# connector.net
KiCad netlist of a schematic drawn in Altium Designer
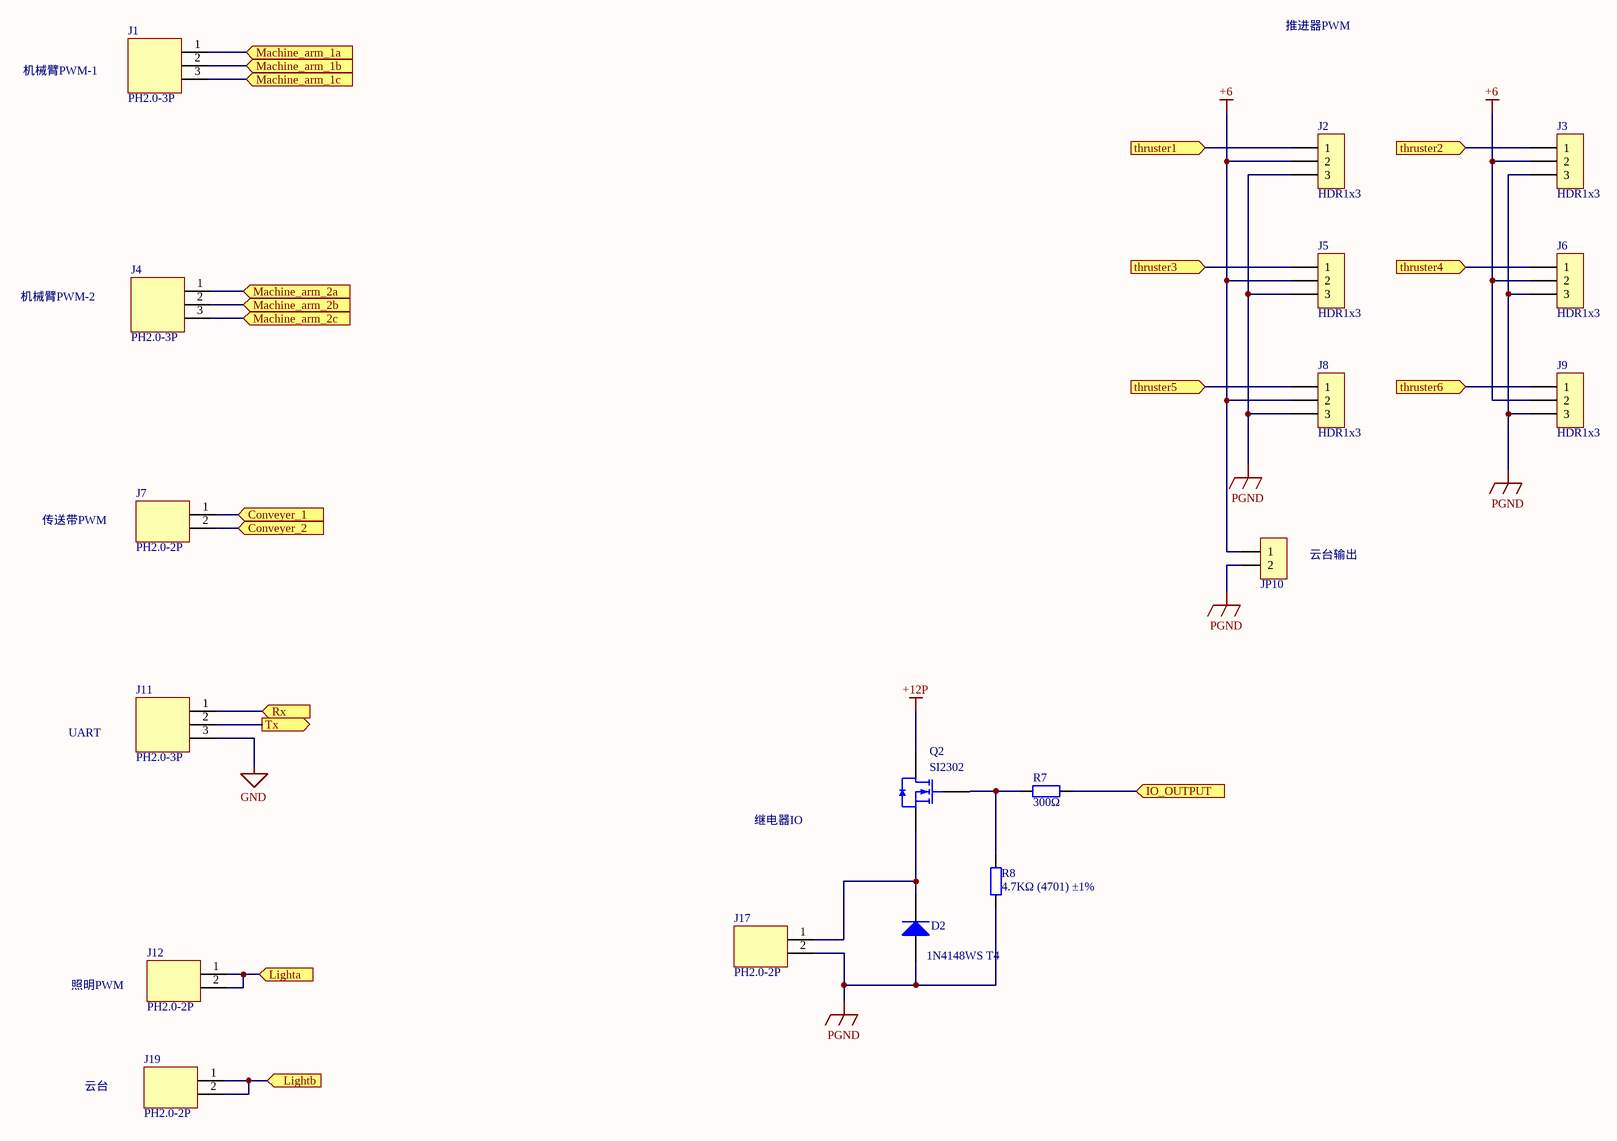
[diagram p0: connector.SchDoc]

(export (version "E")
  (design (tool "Eeschema 10.0.6"))
  (components
    (comp (ref "D2")
      (value "1N4148WS T4")
      (footprint "SOD-323")
      (description "二极管")
      (libsource (lib "Miscellaneous Devices LC") (part "SOD-323 1N4148WS T4"))
    )
    (comp (ref "J1") (value "PH2.0-3P") (footprint "PH2.0-3P") (libsource (lib "PH") (part "PH2.0-3P")))
    (comp (ref "J2")
      (value "HDR1x3")
      (footprint "PIN-3-2.54-1.0")
      (description "Connector")
      (libsource (lib "General") (part "HDR1x3"))
    )
    (comp (ref "J3")
      (value "HDR1x3")
      (footprint "PIN-3-2.54-1.0")
      (description "Connector")
      (libsource (lib "General") (part "HDR1x3"))
    )
    (comp (ref "J4") (value "PH2.0-3P") (footprint "PH2.0-3P") (libsource (lib "PH") (part "PH2.0-3P")))
    (comp (ref "J5")
      (value "HDR1x3")
      (footprint "PIN-3-2.54-1.0")
      (description "Connector")
      (libsource (lib "General") (part "HDR1x3"))
    )
    (comp (ref "J6")
      (value "HDR1x3")
      (footprint "PIN-3-2.54-1.0")
      (description "Connector")
      (libsource (lib "General") (part "HDR1x3"))
    )
    (comp (ref "J7") (value "PH2.0-2P") (footprint "PH2.0-2P") (libsource (lib "PH") (part "PH2.0-2P")))
    (comp (ref "J8")
      (value "HDR1x3")
      (footprint "PIN-3-2.54-1.0")
      (description "Connector")
      (libsource (lib "General") (part "HDR1x3"))
    )
    (comp (ref "J9")
      (value "HDR1x3")
      (footprint "PIN-3-2.54-1.0")
      (description "Connector")
      (libsource (lib "General") (part "HDR1x3"))
    )
    (comp (ref "J11") (value "PH2.0-3P") (footprint "PH2.0-3P") (libsource (lib "PH") (part "PH2.0-3P")))
    (comp (ref "J12") (value "PH2.0-2P") (footprint "PH2.0-2P") (libsource (lib "PH") (part "PH2.0-2P")))
    (comp (ref "J17") (value "PH2.0-2P") (footprint "PH2.0-2P") (libsource (lib "PH") (part "PH2.0-2P")))
    (comp (ref "J19") (value "PH2.0-2P") (footprint "PH2.0-2P") (libsource (lib "PH") (part "PH2.0-2P")))
    (comp (ref "JP10")
      (value "HDR-1X2")
      (footprint "KF128-5.08-2P")
      (description "2P接插件")
      (fields (field (name "版权归属") "源创客"))
      (libsource (lib "4.10 - 接插件-脚距5.08") (part "Header 2"))
    )
    (comp (ref "Q2")
      (value "SI2302")
      (footprint "SOT-23(SOT-23-3)")
      (description "MOS(场效应管)")
      (libsource (lib "Miscellaneous Devices LC") (part "2N7002 7002"))
    )
    (comp (ref "R7")
      (value "300Ω")
      (footprint "0603_R")
      (description "贴片电阻")
      (libsource (lib "Miscellaneous Devices LC") (part "0603 10KΩ (1002) 1%"))
    )
    (comp (ref "R8")
      (value "4.7KΩ (4701) ±1%")
      (footprint "0603_R")
      (description "贴片电阻")
      (libsource (lib "Miscellaneous Devices LC") (part "0603 4.7KΩ (4701) 1%"))
    )
  )
  (nets
    (net (code "1") (name "+6") (class "Default")
      (node (ref "J2") (pin "2") (pinfunction "2_2") (pintype "passive"))
      (node (ref "J3") (pin "2") (pinfunction "2_2") (pintype "passive"))
      (node (ref "J5") (pin "2") (pinfunction "2_2") (pintype "passive"))
      (node (ref "J6") (pin "2") (pinfunction "2_2") (pintype "passive"))
      (node (ref "J8") (pin "2") (pinfunction "2_2") (pintype "passive"))
      (node (ref "J9") (pin "2") (pinfunction "2_2") (pintype "passive"))
      (node (ref "JP10") (pin "1") (pinfunction "1_1") (pintype "passive"))
    )
    (net (code "2") (name "+12P") (class "Default")
      (node (ref "Q2") (pin "3") (pinfunction "D_3") (pintype "passive"))
    )
    (net (code "3") (name "/Conveyer_1") (class "Default")
      (node (ref "J7") (pin "1") (pinfunction "1_1") (pintype "passive"))
    )
    (net (code "4") (name "/Conveyer_2") (class "Default")
      (node (ref "J7") (pin "2") (pinfunction "2_2") (pintype "passive"))
    )
    (net (code "5") (name "/IO_OUTPUT") (class "Default")
      (node (ref "R7") (pin "2") (pinfunction "2_2") (pintype "passive"))
    )
    (net (code "6") (name "/Lighta") (class "Default")
      (node (ref "J12") (pin "1") (pinfunction "1_1") (pintype "passive"))
      (node (ref "J12") (pin "2") (pinfunction "2_2") (pintype "passive"))
    )
    (net (code "7") (name "/Lightb") (class "Default")
      (node (ref "J19") (pin "1") (pinfunction "1_1") (pintype "passive"))
      (node (ref "J19") (pin "2") (pinfunction "2_2") (pintype "passive"))
    )
    (net (code "8") (name "/Machine_arm_1a") (class "Default")
      (node (ref "J1") (pin "1") (pinfunction "1_1") (pintype "passive"))
    )
    (net (code "9") (name "/Machine_arm_1b") (class "Default")
      (node (ref "J1") (pin "2") (pinfunction "2_2") (pintype "passive"))
    )
    (net (code "10") (name "/Machine_arm_1c") (class "Default")
      (node (ref "J1") (pin "3") (pinfunction "3_3") (pintype "passive"))
    )
    (net (code "11") (name "/Machine_arm_2a") (class "Default")
      (node (ref "J4") (pin "1") (pinfunction "1_1") (pintype "passive"))
    )
    (net (code "12") (name "/Machine_arm_2b") (class "Default")
      (node (ref "J4") (pin "2") (pinfunction "2_2") (pintype "passive"))
    )
    (net (code "13") (name "/Machine_arm_2c") (class "Default")
      (node (ref "J4") (pin "3") (pinfunction "3_3") (pintype "passive"))
    )
    (net (code "14") (name "/Rx") (class "Default")
      (node (ref "J11") (pin "1") (pinfunction "1_1") (pintype "passive"))
    )
    (net (code "15") (name "/Tx") (class "Default")
      (node (ref "J11") (pin "2") (pinfunction "2_2") (pintype "passive"))
    )
    (net (code "16") (name "/thruster1") (class "Default")
      (node (ref "J2") (pin "1") (pinfunction "1_1") (pintype "passive"))
    )
    (net (code "17") (name "/thruster2") (class "Default")
      (node (ref "J3") (pin "1") (pinfunction "1_1") (pintype "passive"))
    )
    (net (code "18") (name "/thruster3") (class "Default")
      (node (ref "J5") (pin "1") (pinfunction "1_1") (pintype "passive"))
    )
    (net (code "19") (name "/thruster4") (class "Default")
      (node (ref "J6") (pin "1") (pinfunction "1_1") (pintype "passive"))
    )
    (net (code "20") (name "/thruster5") (class "Default")
      (node (ref "J8") (pin "1") (pinfunction "1_1") (pintype "passive"))
    )
    (net (code "21") (name "/thruster6") (class "Default")
      (node (ref "J9") (pin "1") (pinfunction "1_1") (pintype "passive"))
    )
    (net (code "22") (name "GND") (class "Default")
      (node (ref "J11") (pin "3") (pinfunction "3_3") (pintype "passive"))
    )
    (net (code "23") (name "Net-(D2-K)") (class "Default")
      (node (ref "D2") (pin "2") (pinfunction "K_2") (pintype "passive"))
      (node (ref "J17") (pin "1") (pinfunction "1_1") (pintype "passive"))
      (node (ref "Q2") (pin "2") (pinfunction "S_2") (pintype "passive"))
    )
    (net (code "24") (name "Net-(Q2-G)") (class "Default")
      (node (ref "Q2") (pin "1") (pinfunction "G_1") (pintype "passive"))
      (node (ref "R7") (pin "1") (pinfunction "1_1") (pintype "passive"))
      (node (ref "R8") (pin "2") (pinfunction "2_2") (pintype "passive"))
    )
    (net (code "25") (name "PGND") (class "Default")
      (node (ref "D2") (pin "1") (pinfunction "A_1") (pintype "passive"))
      (node (ref "J17") (pin "2") (pinfunction "2_2") (pintype "passive"))
      (node (ref "J2") (pin "3") (pinfunction "3_3") (pintype "passive"))
      (node (ref "J3") (pin "3") (pinfunction "3_3") (pintype "passive"))
      (node (ref "J5") (pin "3") (pinfunction "3_3") (pintype "passive"))
      (node (ref "J6") (pin "3") (pinfunction "3_3") (pintype "passive"))
      (node (ref "J8") (pin "3") (pinfunction "3_3") (pintype "passive"))
      (node (ref "J9") (pin "3") (pinfunction "3_3") (pintype "passive"))
      (node (ref "JP10") (pin "2") (pinfunction "2_2") (pintype "passive"))
      (node (ref "R8") (pin "1") (pinfunction "1_1") (pintype "passive"))
    )
  )
)
